# BQ29209_breakout_board_V1_1.net
KiCad netlist of a schematic drawn in EAGLE
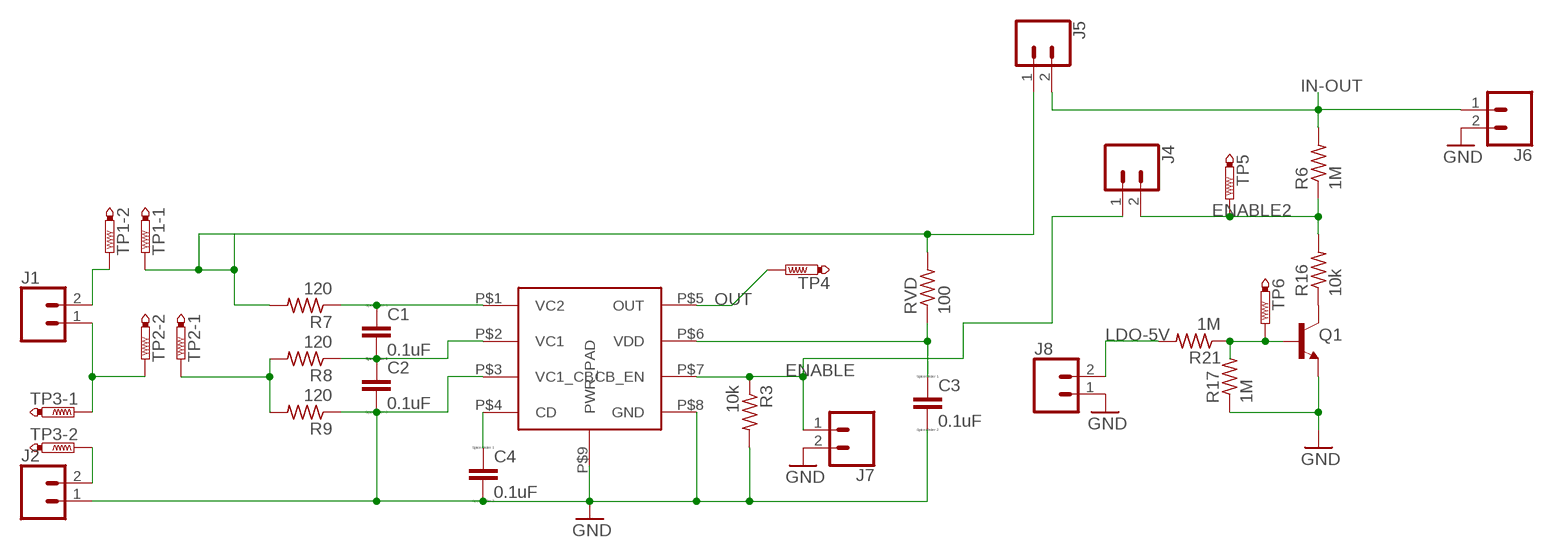
[diagram p0: schematic, sheet 1]

(export (version "E")
  (design (tool "Eeschema 10.0.6"))
  (components
    (comp (ref "C1")
      (value "0.1uF")
      (footprint "eagle-import:C0805")
      (libsource (lib "eagle-import") (part "C"))
    )
    (comp (ref "C2")
      (value "0.1uF")
      (footprint "eagle-import:C0805")
      (libsource (lib "eagle-import") (part "C"))
    )
    (comp (ref "C3")
      (value "0.1uF")
      (footprint "eagle-import:C0805")
      (libsource (lib "eagle-import") (part "C"))
    )
    (comp (ref "C4")
      (value "0.1uF")
      (footprint "eagle-import:C0805")
      (libsource (lib "eagle-import") (part "C"))
    )
    (comp (ref "J1")
      (value "CONN_02")
      (footprint "eagle-import:1X02")
      (libsource (lib "eagle-import") (part "CONN_02"))
    )
    (comp (ref "J2")
      (value "CONN_02")
      (footprint "eagle-import:1X02")
      (libsource (lib "eagle-import") (part "CONN_02"))
    )
    (comp (ref "J4")
      (value "CONN_02")
      (footprint "eagle-import:1X02")
      (libsource (lib "eagle-import") (part "CONN_02"))
    )
    (comp (ref "J5")
      (value "CONN_02")
      (footprint "eagle-import:1X02")
      (libsource (lib "eagle-import") (part "CONN_02"))
    )
    (comp (ref "J6")
      (value "CONN_02")
      (footprint "eagle-import:1X02")
      (libsource (lib "eagle-import") (part "CONN_02"))
    )
    (comp (ref "J7")
      (value "CONN_02")
      (footprint "eagle-import:1X02")
      (libsource (lib "eagle-import") (part "CONN_02"))
    )
    (comp (ref "J8")
      (value "CONN_02")
      (footprint "eagle-import:1X02")
      (libsource (lib "eagle-import") (part "CONN_02"))
    )
    (comp (ref "Q1")
      (value "TRANS_NPN-MMBT2222AL")
      (footprint "eagle-import:SOT23-3")
      (libsource (lib "eagle-import") (part "TRANS_NPN-MMBT2222AL"))
    )
    (comp (ref "R3")
      (value "10k")
      (footprint "eagle-import:R0805")
      (libsource (lib "eagle-import") (part "R-US_R0805"))
    )
    (comp (ref "R6")
      (value "1M")
      (footprint "eagle-import:R0805")
      (libsource (lib "eagle-import") (part "R-US_R0805"))
    )
    (comp (ref "R7")
      (value "120")
      (footprint "eagle-import:R0805")
      (libsource (lib "eagle-import") (part "R-US_R0805"))
    )
    (comp (ref "R8")
      (value "120")
      (footprint "eagle-import:R0805")
      (libsource (lib "eagle-import") (part "R-US_R0805"))
    )
    (comp (ref "R9")
      (value "120")
      (footprint "eagle-import:R0805")
      (libsource (lib "eagle-import") (part "R-US_R0805"))
    )
    (comp (ref "R16")
      (value "10k")
      (footprint "eagle-import:R0805")
      (libsource (lib "eagle-import") (part "R-US_R0805"))
    )
    (comp (ref "R17")
      (value "1M")
      (footprint "eagle-import:M0805")
      (libsource (lib "eagle-import") (part "R-US_M0805"))
    )
    (comp (ref "R21")
      (value "1M")
      (footprint "eagle-import:M0805")
      (libsource (lib "eagle-import") (part "R-US_M0805"))
    )
    (comp (ref "RVD")
      (value "100")
      (footprint "eagle-import:R0805")
      (libsource (lib "eagle-import") (part "R-US_R0805"))
    )
    (comp (ref "TP1")
      (value "PTR2")
      (footprint "eagle-import:P2-38-17")
      (libsource (lib "eagle-import") (part "PTR2"))
    )
    (comp (ref "TP2")
      (value "PTR2")
      (footprint "eagle-import:P2-38-17")
      (libsource (lib "eagle-import") (part "PTR2"))
    )
    (comp (ref "TP3")
      (value "PTR2")
      (footprint "eagle-import:P2-38-17")
      (libsource (lib "eagle-import") (part "PTR2"))
    )
    (comp (ref "TP4")
      (value "PTR1PAD1-13Y")
      (footprint "eagle-import:P1-13Y")
      (libsource (lib "eagle-import") (part "PTR1PAD1-13Y"))
    )
    (comp (ref "TP5")
      (value "PTR1PAD1-13Y")
      (footprint "eagle-import:P1-13Y")
      (libsource (lib "eagle-import") (part "PTR1PAD1-13Y"))
    )
    (comp (ref "TP6")
      (value "PTR1PAD1-13Y")
      (footprint "eagle-import:P1-13Y")
      (libsource (lib "eagle-import") (part "PTR1PAD1-13Y"))
    )
    (comp (ref "U$8")
      (value "BQ29209")
      (footprint "eagle-import:VSON8")
      (libsource (lib "eagle-import") (part "BQ29209"))
    )
  )
  (nets
    (net (code "1") (name "/ENABLE") (class "Default")
      (node (ref "J4") (pin "1") (pinfunction "1_1") (pintype "passive"))
      (node (ref "J7") (pin "1") (pinfunction "1_1") (pintype "passive"))
      (node (ref "R3") (pin "1") (pinfunction "1_1") (pintype "passive"))
      (node (ref "U$8") (pin "P$7") (pinfunction "CB_EN_P$7") (pintype "bidirectional"))
    )
    (net (code "2") (name "/ENABLE2") (class "Default")
      (node (ref "J4") (pin "2") (pinfunction "2_2") (pintype "passive"))
      (node (ref "R16") (pin "2") (pinfunction "2_2") (pintype "passive"))
      (node (ref "R6") (pin "1") (pinfunction "1_1") (pintype "passive"))
      (node (ref "TP5") (pin "TP") (pinfunction "TP_TP") (pintype "input"))
    )
    (net (code "3") (name "/IN-OUT") (class "Default")
      (node (ref "J5") (pin "2") (pinfunction "2_2") (pintype "passive"))
      (node (ref "J6") (pin "1") (pinfunction "1_1") (pintype "passive"))
      (node (ref "R6") (pin "2") (pinfunction "2_2") (pintype "passive"))
    )
    (net (code "4") (name "/LDO-5V") (class "Default")
      (node (ref "J8") (pin "2") (pinfunction "2_2") (pintype "passive"))
      (node (ref "R21") (pin "2") (pinfunction "2_2") (pintype "passive"))
    )
    (net (code "5") (name "/OUT") (class "Default")
      (node (ref "TP4") (pin "TP") (pinfunction "TP_TP") (pintype "input"))
      (node (ref "U$8") (pin "P$5") (pinfunction "OUT_P$5") (pintype "bidirectional"))
    )
    (net (code "6") (name "GND") (class "Default")
      (node (ref "C2") (pin "2") (pinfunction "2_2") (pintype "passive"))
      (node (ref "C3") (pin "2") (pinfunction "2_2") (pintype "passive"))
      (node (ref "C4") (pin "2") (pinfunction "2_2") (pintype "passive"))
      (node (ref "J2") (pin "1") (pinfunction "1_1") (pintype "passive"))
      (node (ref "J6") (pin "2") (pinfunction "2_2") (pintype "passive"))
      (node (ref "J7") (pin "2") (pinfunction "2_2") (pintype "passive"))
      (node (ref "J8") (pin "1") (pinfunction "1_1") (pintype "passive"))
      (node (ref "Q1") (pin "2") (pinfunction "E_2") (pintype "passive"))
      (node (ref "R17") (pin "1") (pinfunction "1_1") (pintype "passive"))
      (node (ref "R3") (pin "2") (pinfunction "2_2") (pintype "passive"))
      (node (ref "R9") (pin "1") (pinfunction "1_1") (pintype "passive"))
      (node (ref "U$8") (pin "P$3") (pinfunction "VC1_CB_P$3") (pintype "bidirectional"))
      (node (ref "U$8") (pin "P$8") (pinfunction "GND_P$8") (pintype "bidirectional"))
      (node (ref "U$8") (pin "P$9") (pinfunction "PWR_PAD_P$9") (pintype "bidirectional"))
    )
    (net (code "7") (name "Net-(Q1-B)") (class "Default")
      (node (ref "Q1") (pin "1") (pinfunction "B_1") (pintype "passive"))
      (node (ref "R17") (pin "2") (pinfunction "2_2") (pintype "passive"))
      (node (ref "R21") (pin "1") (pinfunction "1_1") (pintype "passive"))
      (node (ref "TP6") (pin "TP") (pinfunction "TP_TP") (pintype "input"))
    )
    (net (code "8") (name "Net-(Q1-C)") (class "Default")
      (node (ref "Q1") (pin "3") (pinfunction "C_3") (pintype "passive"))
      (node (ref "R16") (pin "1") (pinfunction "1_1") (pintype "passive"))
    )
    (net (code "9") (name "Net-(TP1A-TP)") (class "Default")
      (node (ref "J5") (pin "1") (pinfunction "1_1") (pintype "passive"))
      (node (ref "R7") (pin "2") (pinfunction "2_2") (pintype "passive"))
      (node (ref "RVD") (pin "2") (pinfunction "2_2") (pintype "passive"))
      (node (ref "TP1") (pin "TP-1") (pinfunction "TP_TP-1") (pintype "input"))
    )
    (net (code "10") (name "Net-(TP1B-TP)") (class "Default")
      (node (ref "J1") (pin "2") (pinfunction "2_2") (pintype "passive"))
      (node (ref "TP1") (pin "TP-2") (pinfunction "TP_TP-2") (pintype "input"))
    )
    (net (code "11") (name "Net-(TP2A-TP)") (class "Default")
      (node (ref "R8") (pin "2") (pinfunction "2_2") (pintype "passive"))
      (node (ref "R9") (pin "2") (pinfunction "2_2") (pintype "passive"))
      (node (ref "TP2") (pin "TP-1") (pinfunction "TP_TP-1") (pintype "input"))
    )
    (net (code "12") (name "Net-(TP2B-TP)") (class "Default")
      (node (ref "J1") (pin "1") (pinfunction "1_1") (pintype "passive"))
      (node (ref "TP2") (pin "TP-2") (pinfunction "TP_TP-2") (pintype "input"))
      (node (ref "TP3") (pin "TP-1") (pinfunction "TP_TP-1") (pintype "input"))
    )
    (net (code "13") (name "Net-(TP3B-TP)") (class "Default")
      (node (ref "J2") (pin "2") (pinfunction "2_2") (pintype "passive"))
      (node (ref "TP3") (pin "TP-2") (pinfunction "TP_TP-2") (pintype "input"))
    )
    (net (code "14") (name "Net-(U$8-CD)") (class "Default")
      (node (ref "C4") (pin "1") (pinfunction "1_1") (pintype "passive"))
      (node (ref "U$8") (pin "P$4") (pinfunction "CD_P$4") (pintype "bidirectional"))
    )
    (net (code "15") (name "Net-(U$8-VC1)") (class "Default")
      (node (ref "C1") (pin "2") (pinfunction "2_2") (pintype "passive"))
      (node (ref "C2") (pin "1") (pinfunction "1_1") (pintype "passive"))
      (node (ref "R8") (pin "1") (pinfunction "1_1") (pintype "passive"))
      (node (ref "U$8") (pin "P$2") (pinfunction "VC1_P$2") (pintype "bidirectional"))
    )
    (net (code "16") (name "Net-(U$8-VC2)") (class "Default")
      (node (ref "C1") (pin "1") (pinfunction "1_1") (pintype "passive"))
      (node (ref "R7") (pin "1") (pinfunction "1_1") (pintype "passive"))
      (node (ref "U$8") (pin "P$1") (pinfunction "VC2_P$1") (pintype "bidirectional"))
    )
    (net (code "17") (name "Net-(U$8-VDD)") (class "Default")
      (node (ref "C3") (pin "1") (pinfunction "1_1") (pintype "passive"))
      (node (ref "RVD") (pin "1") (pinfunction "1_1") (pintype "passive"))
      (node (ref "U$8") (pin "P$6") (pinfunction "VDD_P$6") (pintype "bidirectional"))
    )
  )
)
